# ProPrj_esp_artnet_DMX_2024-10-07.net
KiCad netlist of a schematic drawn in EasyEDA Pro
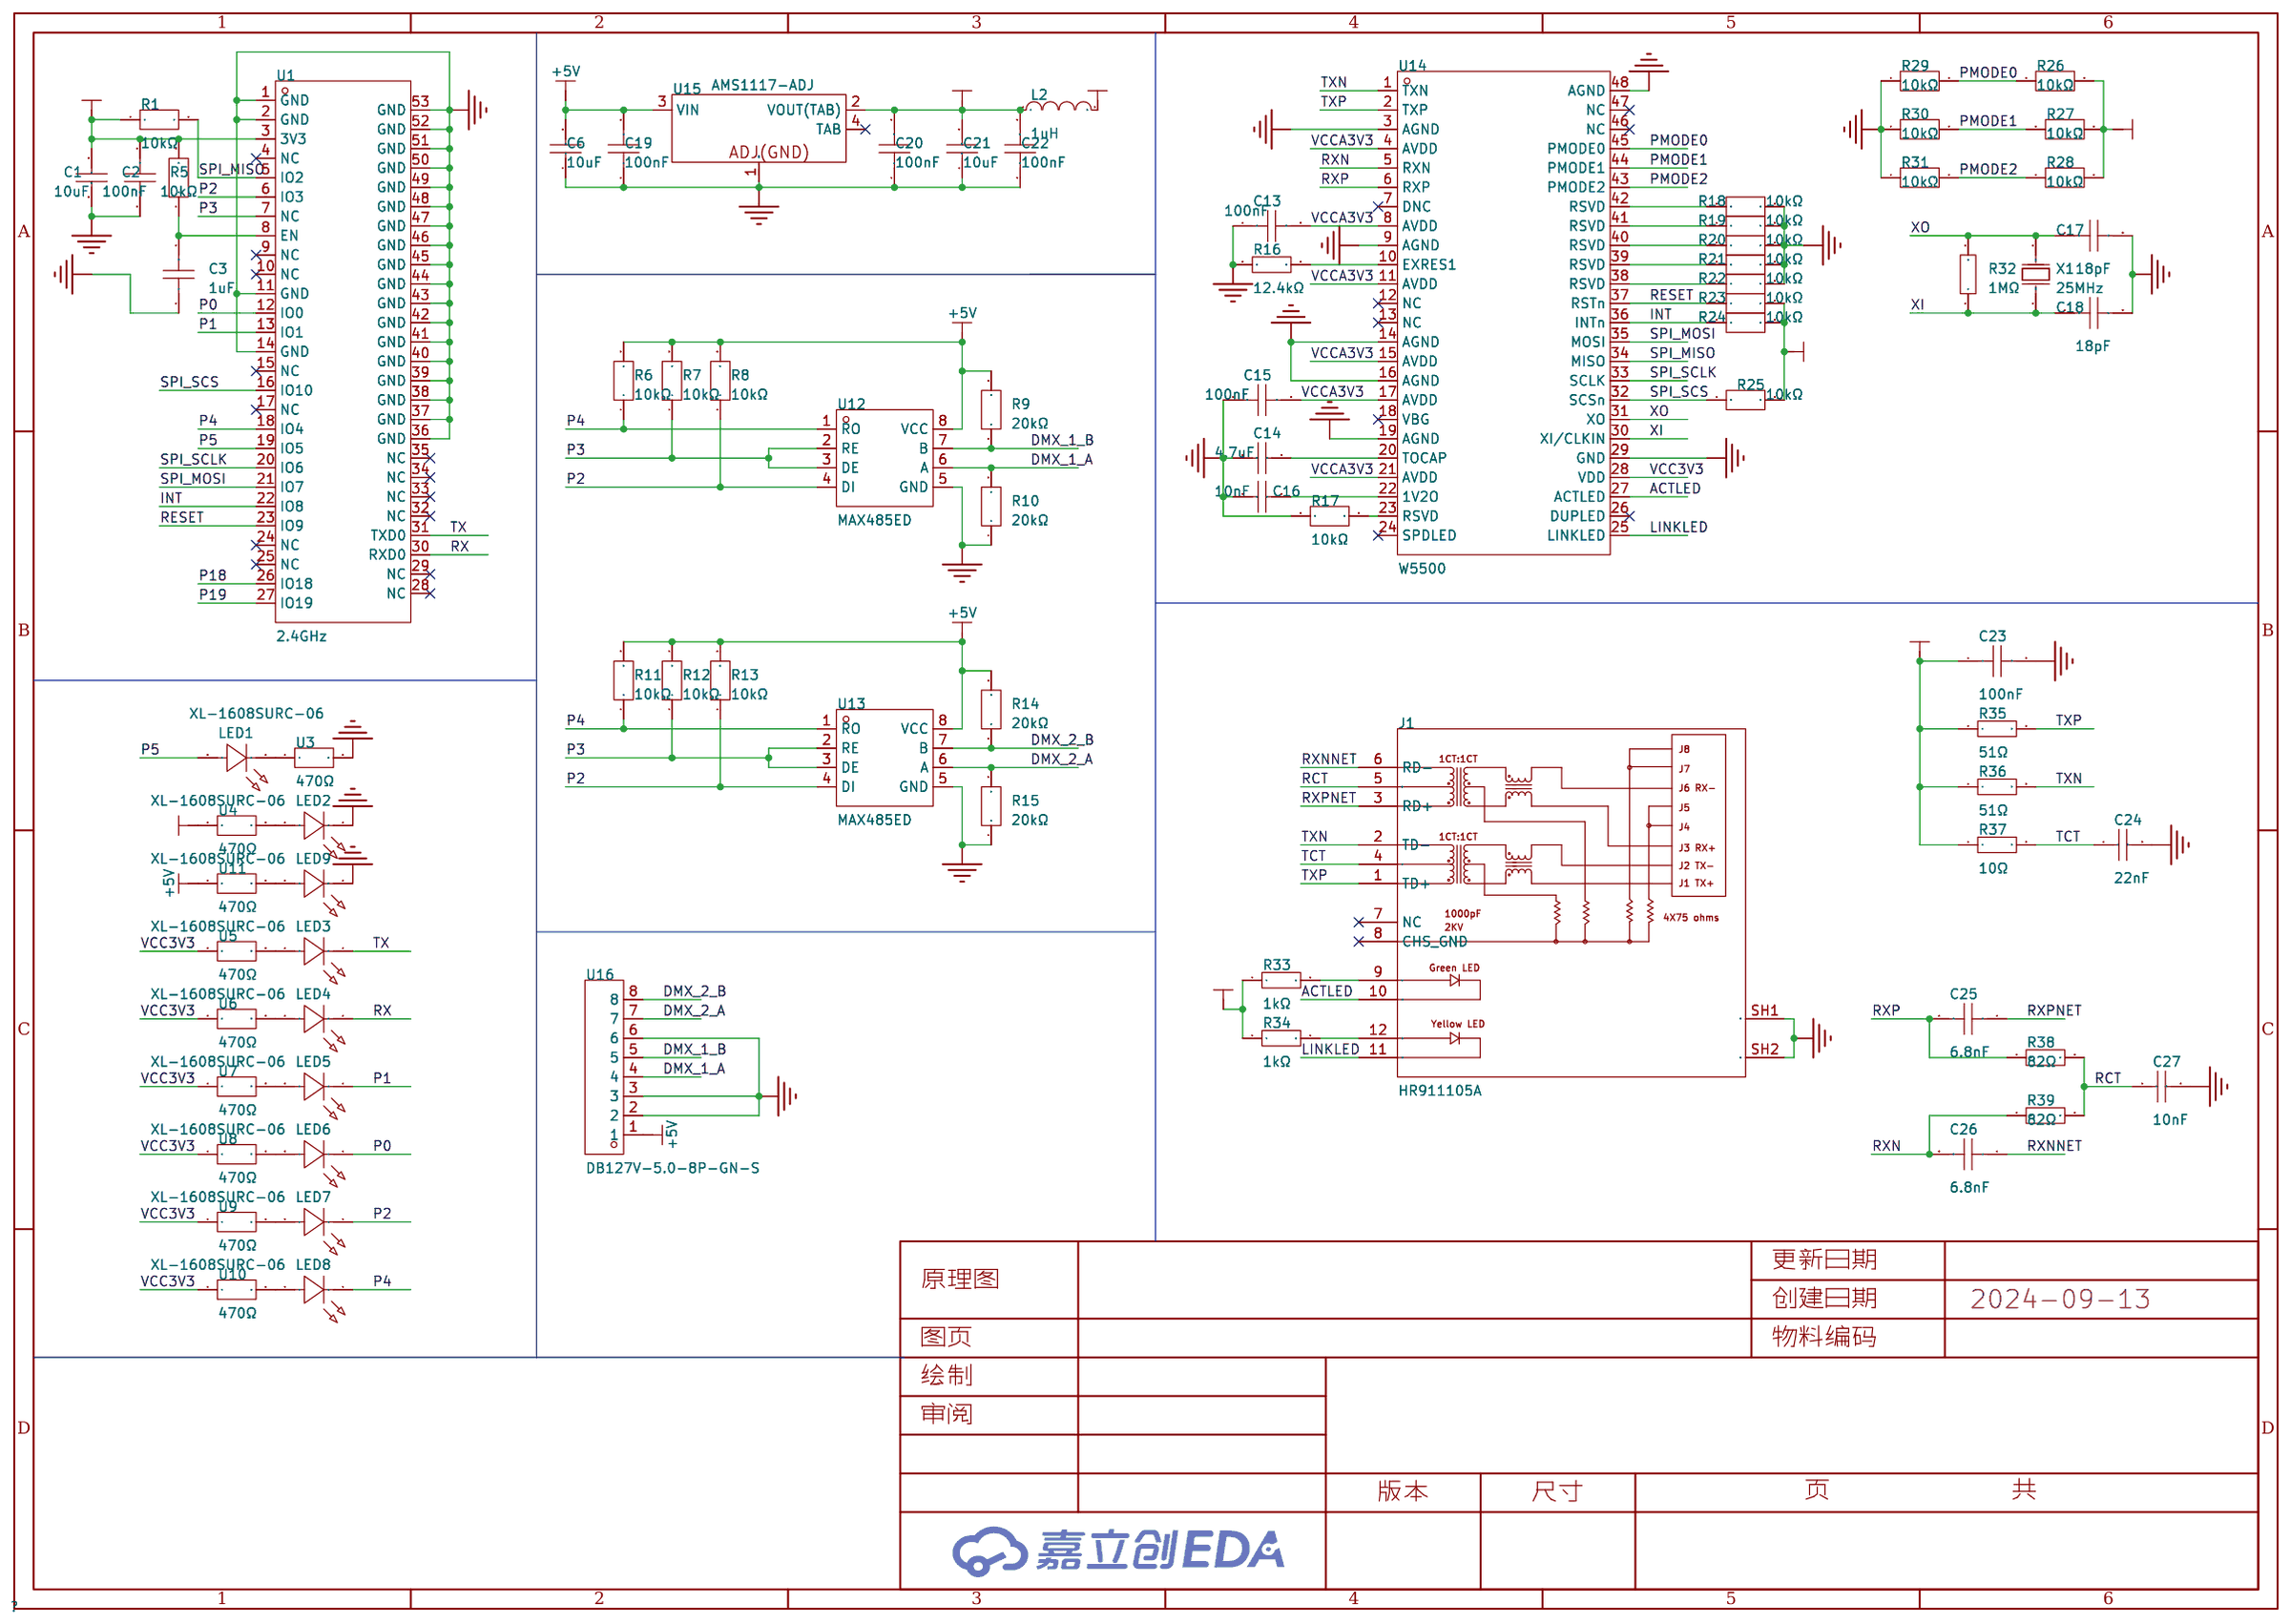
[diagram p0: schematic sheet]

(export (version "E")
  (design (tool "Eeschema 10.0.6"))
  (components
    (comp (ref "C1")
      (value "10uF")
      (footprint "easyedapro:C0805")
      (description "容值:10uF;精度:±10%;额定电压:10V;材质(温度系数):X5R;")
      (fields
        (field (name "Manufacturer Part") "CL21A106KPFNNNE")
        (field (name "Manufacturer") "SAMSUNG(三星)")
      )
      (libsource (lib "easyedapro") (part "CL21A106KPFNNNE"))
    )
    (comp (ref "C2")
      (value "100nF")
      (footprint "easyedapro:C0603")
      (description "容值:100nF;精度:±10%;额定电压:50V;材质(温度系数):X7R;")
      (fields
        (field (name "Manufacturer Part") "CGA0603X7R104K500JT")
        (field (name "Manufacturer") "HRE(芯声)")
      )
      (libsource (lib "easyedapro") (part "CGA0603X7R104K500JT"))
    )
    (comp (ref "C3")
      (value "1uF")
      (footprint "easyedapro:C0603")
      (description "容值:1uF;精度:±10%;额定电压:50V;材质(温度系数):X5R;")
      (fields
        (field (name "Manufacturer Part") "CL10A105KB8NNNC")
        (field (name "Manufacturer") "SAMSUNG(三星)")
      )
      (libsource (lib "easyedapro") (part "CL10A105KB8NNNC"))
    )
    (comp (ref "C6")
      (value "10uF")
      (footprint "easyedapro:C0805")
      (description "容值:10uF;精度:±10%;额定电压:10V;材质(温度系数):X5R;")
      (fields
        (field (name "Manufacturer Part") "CL21A106KPFNNNE")
        (field (name "Manufacturer") "SAMSUNG(三星)")
      )
      (libsource (lib "easyedapro") (part "CL21A106KPFNNNE"))
    )
    (comp (ref "C13")
      (value "100nF")
      (footprint "easyedapro:C0603")
      (description "容值:100nF;精度:±10%;额定电压:50V;材质(温度系数):X7R;")
      (fields
        (field (name "Manufacturer Part") "CGA0603X7R104K500JT")
        (field (name "Manufacturer") "HRE(芯声)")
      )
      (libsource (lib "easyedapro") (part "CGA0603X7R104K500JT"))
    )
    (comp (ref "C14")
      (value "4.7uF")
      (footprint "easyedapro:C0603")
      (description "容值:4.7uF;精度:±10%;额定电压:16V;材质(温度系数):X5R;")
      (fields
        (field (name "Manufacturer Part") "CL10A475KO8NNNC")
        (field (name "Manufacturer") "SAMSUNG(三星)")
      )
      (libsource (lib "easyedapro") (part "CL10A475KO8NNNC"))
    )
    (comp (ref "C15")
      (value "100nF")
      (footprint "easyedapro:C0603")
      (description "容值:100nF;精度:±10%;额定电压:50V;材质(温度系数):X7R;")
      (fields
        (field (name "Manufacturer Part") "CGA0603X7R104K500JT")
        (field (name "Manufacturer") "HRE(芯声)")
      )
      (libsource (lib "easyedapro") (part "CGA0603X7R104K500JT"))
    )
    (comp (ref "C16")
      (value "10nF")
      (footprint "easyedapro:C0603")
      (description "容值:10nF;精度:±10%;额定电压:50V;材质(温度系数):X7R;")
      (fields
        (field (name "Manufacturer Part") "CC0603KRX7R9BB103")
        (field (name "Manufacturer") "YAGEO(国巨)")
      )
      (libsource (lib "easyedapro") (part "CC0603KRX7R9BB103"))
    )
    (comp (ref "C17")
      (value "18pF")
      (footprint "easyedapro:C0603")
      (description "容值:18pF;精度:±5%;额定电压:50V;材质(温度系数):C0G;")
      (fields
        (field (name "Manufacturer Part") "FCC0603N180J500CT")
        (field (name "Manufacturer") "FOJAN(富捷)")
      )
      (libsource (lib "easyedapro") (part "FCC0603N180J500CT"))
    )
    (comp (ref "C18")
      (value "18pF")
      (footprint "easyedapro:C0603")
      (description "容值:18pF;精度:±5%;额定电压:50V;材质(温度系数):C0G;")
      (fields
        (field (name "Manufacturer Part") "FCC0603N180J500CT")
        (field (name "Manufacturer") "FOJAN(富捷)")
      )
      (libsource (lib "easyedapro") (part "FCC0603N180J500CT"))
    )
    (comp (ref "C19")
      (value "100nF")
      (footprint "easyedapro:C0603")
      (description "容值:100nF;精度:±10%;额定电压:50V;材质(温度系数):X7R;")
      (fields
        (field (name "Manufacturer Part") "CGA0603X7R104K500JT")
        (field (name "Manufacturer") "HRE(芯声)")
      )
      (libsource (lib "easyedapro") (part "CGA0603X7R104K500JT"))
    )
    (comp (ref "C20")
      (value "100nF")
      (footprint "easyedapro:C0603")
      (description "容值:100nF;精度:±10%;额定电压:50V;材质(温度系数):X7R;")
      (fields
        (field (name "Manufacturer Part") "CGA0603X7R104K500JT")
        (field (name "Manufacturer") "HRE(芯声)")
      )
      (libsource (lib "easyedapro") (part "CGA0603X7R104K500JT"))
    )
    (comp (ref "C21")
      (value "10uF")
      (footprint "easyedapro:C0805")
      (description "容值:10uF;精度:±10%;额定电压:10V;材质(温度系数):X5R;")
      (fields
        (field (name "Manufacturer Part") "CL21A106KPFNNNE")
        (field (name "Manufacturer") "SAMSUNG(三星)")
      )
      (libsource (lib "easyedapro") (part "CL21A106KPFNNNE"))
    )
    (comp (ref "C22")
      (value "100nF")
      (footprint "easyedapro:C0603")
      (description "容值:100nF;精度:±10%;额定电压:50V;材质(温度系数):X7R;")
      (fields
        (field (name "Manufacturer Part") "CGA0603X7R104K500JT")
        (field (name "Manufacturer") "HRE(芯声)")
      )
      (libsource (lib "easyedapro") (part "CGA0603X7R104K500JT"))
    )
    (comp (ref "C23")
      (value "100nF")
      (footprint "easyedapro:C0603")
      (description "容值:100nF;精度:±10%;额定电压:50V;材质(温度系数):X7R;")
      (fields
        (field (name "Manufacturer Part") "CGA0603X7R104K500JT")
        (field (name "Manufacturer") "HRE(芯声)")
      )
      (libsource (lib "easyedapro") (part "CGA0603X7R104K500JT"))
    )
    (comp (ref "C24")
      (value "22nF")
      (footprint "easyedapro:C0603")
      (description "容值:22nF;精度:±10%;额定电压:50V;材质(温度系数):X7R;")
      (fields
        (field (name "Manufacturer Part") "CL10B223KB8NNNC")
        (field (name "Manufacturer") "SAMSUNG(三星)")
      )
      (libsource (lib "easyedapro") (part "CL10B223KB8NNNC"))
    )
    (comp (ref "C25")
      (value "6.8nF")
      (footprint "easyedapro:C0603")
      (description "容值:6.8nF;精度:±5%;额定电压:50V;材质(温度系数):C0G;")
      (fields
        (field (name "Manufacturer Part") "GRM1885C1H682JA01D")
        (field (name "Manufacturer") "muRata(村田)")
      )
      (libsource (lib "easyedapro") (part "GRM1885C1H682JA01D"))
    )
    (comp (ref "C26")
      (value "6.8nF")
      (footprint "easyedapro:C0603")
      (description "容值:6.8nF;精度:±5%;额定电压:50V;材质(温度系数):C0G;")
      (fields
        (field (name "Manufacturer Part") "GRM1885C1H682JA01D")
        (field (name "Manufacturer") "muRata(村田)")
      )
      (libsource (lib "easyedapro") (part "GRM1885C1H682JA01D"))
    )
    (comp (ref "C27")
      (value "10nF")
      (footprint "easyedapro:C0603")
      (description "容值:10nF;精度:±10%;额定电压:50V;材质(温度系数):X7R;")
      (fields
        (field (name "Manufacturer Part") "CC0603KRX7R9BB103")
        (field (name "Manufacturer") "YAGEO(国巨)")
      )
      (libsource (lib "easyedapro") (part "CC0603KRX7R9BB103"))
    )
    (comp (ref "J1")
      (value "HR911105A")
      (footprint "easyedapro:RJ45-TH_HR911105A")
      (description "连接器类型:RJ45插座;端口数量:1;安装方式:-;屏蔽:-;LED:带LED;等级:-;触头材质:-;触头镀层:-;工作温度范围:-;焊接温度(最大值):-;")
      (fields (field (name "Manufacturer") "HANRUN(汉仁)"))
      (libsource (lib "easyedapro") (part "HR911105A_C12074"))
    )
    (comp (ref "L2")
      (value "1uH")
      (footprint "easyedapro:IND-SMD_L4.4-W4.2")
      (description "电感值:1uH;精度:±20%;额定电流:6A;饱和电流(Isat):7A;类型:一体成型电感;")
      (fields (field (name "Manufacturer Part") "FXL0420-1R0-M") (field (name "Manufacturer") "cjiang(长江微电)"))
      (libsource (lib "easyedapro") (part "FXL0420-1R0-M"))
    )
    (comp (ref "LED1")
      (value "XL-1608SURC-06")
      (footprint "easyedapro:LED0603-RD_RED")
      (description "发光颜色:红色;功率:55mW;正向电流:25mA;主波长:617nm~621nm;透镜颜色:无色透明透镜;色温:-;发光角度:120°;载带方式:正贴;工作温度:-30°C~+85°C;")
      (fields (field (name "Manufacturer") "XINGLIGHT(成兴光)"))
      (libsource (lib "easyedapro") (part "XL-1608SURC-06"))
    )
    (comp (ref "LED2")
      (value "XL-1608SURC-06")
      (footprint "easyedapro:LED0603-RD_RED")
      (description "发光颜色:红色;功率:55mW;正向电流:25mA;主波长:617nm~621nm;透镜颜色:无色透明透镜;色温:-;发光角度:120°;载带方式:正贴;工作温度:-30°C~+85°C;")
      (fields (field (name "Manufacturer") "XINGLIGHT(成兴光)"))
      (libsource (lib "easyedapro") (part "XL-1608SURC-06"))
    )
    (comp (ref "LED3")
      (value "XL-1608SURC-06")
      (footprint "easyedapro:LED0603-RD_RED")
      (description "发光颜色:红色;功率:55mW;正向电流:25mA;主波长:617nm~621nm;透镜颜色:无色透明透镜;色温:-;发光角度:120°;载带方式:正贴;工作温度:-30°C~+85°C;")
      (fields (field (name "Manufacturer") "XINGLIGHT(成兴光)"))
      (libsource (lib "easyedapro") (part "XL-1608SURC-06"))
    )
    (comp (ref "LED4")
      (value "XL-1608SURC-06")
      (footprint "easyedapro:LED0603-RD_RED")
      (description "发光颜色:红色;功率:55mW;正向电流:25mA;主波长:617nm~621nm;透镜颜色:无色透明透镜;色温:-;发光角度:120°;载带方式:正贴;工作温度:-30°C~+85°C;")
      (fields (field (name "Manufacturer") "XINGLIGHT(成兴光)"))
      (libsource (lib "easyedapro") (part "XL-1608SURC-06"))
    )
    (comp (ref "LED5")
      (value "XL-1608SURC-06")
      (footprint "easyedapro:LED0603-RD_RED")
      (description "发光颜色:红色;功率:55mW;正向电流:25mA;主波长:617nm~621nm;透镜颜色:无色透明透镜;色温:-;发光角度:120°;载带方式:正贴;工作温度:-30°C~+85°C;")
      (fields (field (name "Manufacturer") "XINGLIGHT(成兴光)"))
      (libsource (lib "easyedapro") (part "XL-1608SURC-06"))
    )
    (comp (ref "LED6")
      (value "XL-1608SURC-06")
      (footprint "easyedapro:LED0603-RD_RED")
      (description "发光颜色:红色;功率:55mW;正向电流:25mA;主波长:617nm~621nm;透镜颜色:无色透明透镜;色温:-;发光角度:120°;载带方式:正贴;工作温度:-30°C~+85°C;")
      (fields (field (name "Manufacturer") "XINGLIGHT(成兴光)"))
      (libsource (lib "easyedapro") (part "XL-1608SURC-06"))
    )
    (comp (ref "LED7")
      (value "XL-1608SURC-06")
      (footprint "easyedapro:LED0603-RD_RED")
      (description "发光颜色:红色;功率:55mW;正向电流:25mA;主波长:617nm~621nm;透镜颜色:无色透明透镜;色温:-;发光角度:120°;载带方式:正贴;工作温度:-30°C~+85°C;")
      (fields (field (name "Manufacturer") "XINGLIGHT(成兴光)"))
      (libsource (lib "easyedapro") (part "XL-1608SURC-06"))
    )
    (comp (ref "LED8")
      (value "XL-1608SURC-06")
      (footprint "easyedapro:LED0603-RD_RED")
      (description "发光颜色:红色;功率:55mW;正向电流:25mA;主波长:617nm~621nm;透镜颜色:无色透明透镜;色温:-;发光角度:120°;载带方式:正贴;工作温度:-30°C~+85°C;")
      (fields (field (name "Manufacturer") "XINGLIGHT(成兴光)"))
      (libsource (lib "easyedapro") (part "XL-1608SURC-06"))
    )
    (comp (ref "LED9")
      (value "XL-1608SURC-06")
      (footprint "easyedapro:LED0603-RD_RED")
      (description "发光颜色:红色;功率:55mW;正向电流:25mA;主波长:617nm~621nm;透镜颜色:无色透明透镜;色温:-;发光角度:120°;载带方式:正贴;工作温度:-30°C~+85°C;")
      (fields (field (name "Manufacturer") "XINGLIGHT(成兴光)"))
      (libsource (lib "easyedapro") (part "XL-1608SURC-06"))
    )
    (comp (ref "R1")
      (value "10kΩ")
      (footprint "easyedapro:R0603")
      (description "电阻类型:厚膜电阻;阻值:10kΩ;精度:±5%;功率:100mW;最大工作电压:75V;温度系数:±100ppm/°C;")
      (fields (field (name "Manufacturer Part") "FRC0603J103TS") (field (name "Manufacturer") "FOJAN(富捷)"))
      (libsource (lib "easyedapro") (part "FRC0603J103TS"))
    )
    (comp (ref "R5")
      (value "10kΩ")
      (footprint "easyedapro:R0603")
      (description "电阻类型:厚膜电阻;阻值:10kΩ;精度:±5%;功率:100mW;最大工作电压:75V;温度系数:±100ppm/°C;")
      (fields (field (name "Manufacturer Part") "FRC0603J103TS") (field (name "Manufacturer") "FOJAN(富捷)"))
      (libsource (lib "easyedapro") (part "FRC0603J103TS"))
    )
    (comp (ref "R6")
      (value "10kΩ")
      (footprint "easyedapro:R0603")
      (description "电阻类型:厚膜电阻;阻值:10kΩ;精度:±5%;功率:100mW;最大工作电压:75V;温度系数:±100ppm/°C;")
      (fields (field (name "Manufacturer Part") "FRC0603J103TS") (field (name "Manufacturer") "FOJAN(富捷)"))
      (libsource (lib "easyedapro") (part "FRC0603J103TS"))
    )
    (comp (ref "R7")
      (value "10kΩ")
      (footprint "easyedapro:R0603")
      (description "电阻类型:厚膜电阻;阻值:10kΩ;精度:±5%;功率:100mW;最大工作电压:75V;温度系数:±100ppm/°C;")
      (fields (field (name "Manufacturer Part") "FRC0603J103TS") (field (name "Manufacturer") "FOJAN(富捷)"))
      (libsource (lib "easyedapro") (part "FRC0603J103TS"))
    )
    (comp (ref "R8")
      (value "10kΩ")
      (footprint "easyedapro:R0603")
      (description "电阻类型:厚膜电阻;阻值:10kΩ;精度:±5%;功率:100mW;最大工作电压:75V;温度系数:±100ppm/°C;")
      (fields (field (name "Manufacturer Part") "FRC0603J103TS") (field (name "Manufacturer") "FOJAN(富捷)"))
      (libsource (lib "easyedapro") (part "FRC0603J103TS"))
    )
    (comp (ref "R9")
      (value "20kΩ")
      (footprint "easyedapro:R0603")
      (description "电阻类型:薄膜电阻;阻值:20kΩ;精度:±0.1%;功率:100mW;最大工作电压:75V;温度系数:±25ppm/°C;")
      (fields (field (name "Manufacturer Part") "RT0603BRD0720KL") (field (name "Manufacturer") "YAGEO(国巨)"))
      (libsource (lib "easyedapro") (part "RT0603BRD0720KL"))
    )
    (comp (ref "R10")
      (value "20kΩ")
      (footprint "easyedapro:R0603")
      (description "电阻类型:薄膜电阻;阻值:20kΩ;精度:±0.1%;功率:100mW;最大工作电压:75V;温度系数:±25ppm/°C;")
      (fields (field (name "Manufacturer Part") "RT0603BRD0720KL") (field (name "Manufacturer") "YAGEO(国巨)"))
      (libsource (lib "easyedapro") (part "RT0603BRD0720KL"))
    )
    (comp (ref "R11")
      (value "10kΩ")
      (footprint "easyedapro:R0603")
      (description "电阻类型:厚膜电阻;阻值:10kΩ;精度:±5%;功率:100mW;最大工作电压:75V;温度系数:±100ppm/°C;")
      (fields (field (name "Manufacturer Part") "FRC0603J103TS") (field (name "Manufacturer") "FOJAN(富捷)"))
      (libsource (lib "easyedapro") (part "FRC0603J103TS"))
    )
    (comp (ref "R12")
      (value "10kΩ")
      (footprint "easyedapro:R0603")
      (description "电阻类型:厚膜电阻;阻值:10kΩ;精度:±5%;功率:100mW;最大工作电压:75V;温度系数:±100ppm/°C;")
      (fields (field (name "Manufacturer Part") "FRC0603J103TS") (field (name "Manufacturer") "FOJAN(富捷)"))
      (libsource (lib "easyedapro") (part "FRC0603J103TS"))
    )
    (comp (ref "R13")
      (value "10kΩ")
      (footprint "easyedapro:R0603")
      (description "电阻类型:厚膜电阻;阻值:10kΩ;精度:±5%;功率:100mW;最大工作电压:75V;温度系数:±100ppm/°C;")
      (fields (field (name "Manufacturer Part") "FRC0603J103TS") (field (name "Manufacturer") "FOJAN(富捷)"))
      (libsource (lib "easyedapro") (part "FRC0603J103TS"))
    )
    (comp (ref "R14")
      (value "20kΩ")
      (footprint "easyedapro:R0603")
      (description "电阻类型:薄膜电阻;阻值:20kΩ;精度:±0.1%;功率:100mW;最大工作电压:75V;温度系数:±25ppm/°C;")
      (fields (field (name "Manufacturer Part") "RT0603BRD0720KL") (field (name "Manufacturer") "YAGEO(国巨)"))
      (libsource (lib "easyedapro") (part "RT0603BRD0720KL"))
    )
    (comp (ref "R15")
      (value "20kΩ")
      (footprint "easyedapro:R0603")
      (description "电阻类型:薄膜电阻;阻值:20kΩ;精度:±0.1%;功率:100mW;最大工作电压:75V;温度系数:±25ppm/°C;")
      (fields (field (name "Manufacturer Part") "RT0603BRD0720KL") (field (name "Manufacturer") "YAGEO(国巨)"))
      (libsource (lib "easyedapro") (part "RT0603BRD0720KL"))
    )
    (comp (ref "R16")
      (value "12.4kΩ")
      (footprint "easyedapro:R0603")
      (description "电阻类型:厚膜电阻;阻值:12.4kΩ;精度:±1%;功率:100mW;最大工作电压:75V;温度系数:±100ppm/°C;")
      (fields
        (field (name "Manufacturer Part") "0603WAF1242T5E")
        (field (name "Manufacturer") "UNI-ROYAL(厚声)")
      )
      (libsource (lib "easyedapro") (part "0603WAF1242T5E"))
    )
    (comp (ref "R17")
      (value "10kΩ")
      (footprint "easyedapro:R0603")
      (description "电阻类型:厚膜电阻;阻值:10kΩ;精度:±5%;功率:100mW;最大工作电压:75V;温度系数:±100ppm/°C;")
      (fields (field (name "Manufacturer Part") "FRC0603J103TS") (field (name "Manufacturer") "FOJAN(富捷)"))
      (libsource (lib "easyedapro") (part "FRC0603J103TS"))
    )
    (comp (ref "R18")
      (value "10kΩ")
      (footprint "easyedapro:R0603")
      (description "电阻类型:厚膜电阻;阻值:10kΩ;精度:±5%;功率:100mW;最大工作电压:75V;温度系数:±100ppm/°C;")
      (fields (field (name "Manufacturer Part") "FRC0603J103TS") (field (name "Manufacturer") "FOJAN(富捷)"))
      (libsource (lib "easyedapro") (part "FRC0603J103TS"))
    )
    (comp (ref "R19")
      (value "10kΩ")
      (footprint "easyedapro:R0603")
      (description "电阻类型:厚膜电阻;阻值:10kΩ;精度:±5%;功率:100mW;最大工作电压:75V;温度系数:±100ppm/°C;")
      (fields (field (name "Manufacturer Part") "FRC0603J103TS") (field (name "Manufacturer") "FOJAN(富捷)"))
      (libsource (lib "easyedapro") (part "FRC0603J103TS"))
    )
    (comp (ref "R20")
      (value "10kΩ")
      (footprint "easyedapro:R0603")
      (description "电阻类型:厚膜电阻;阻值:10kΩ;精度:±5%;功率:100mW;最大工作电压:75V;温度系数:±100ppm/°C;")
      (fields (field (name "Manufacturer Part") "FRC0603J103TS") (field (name "Manufacturer") "FOJAN(富捷)"))
      (libsource (lib "easyedapro") (part "FRC0603J103TS"))
    )
    (comp (ref "R21")
      (value "10kΩ")
      (footprint "easyedapro:R0603")
      (description "电阻类型:厚膜电阻;阻值:10kΩ;精度:±5%;功率:100mW;最大工作电压:75V;温度系数:±100ppm/°C;")
      (fields (field (name "Manufacturer Part") "FRC0603J103TS") (field (name "Manufacturer") "FOJAN(富捷)"))
      (libsource (lib "easyedapro") (part "FRC0603J103TS"))
    )
    (comp (ref "R22")
      (value "10kΩ")
      (footprint "easyedapro:R0603")
      (description "电阻类型:厚膜电阻;阻值:10kΩ;精度:±5%;功率:100mW;最大工作电压:75V;温度系数:±100ppm/°C;")
      (fields (field (name "Manufacturer Part") "FRC0603J103TS") (field (name "Manufacturer") "FOJAN(富捷)"))
      (libsource (lib "easyedapro") (part "FRC0603J103TS"))
    )
    (comp (ref "R23")
      (value "10kΩ")
      (footprint "easyedapro:R0603")
      (description "电阻类型:厚膜电阻;阻值:10kΩ;精度:±5%;功率:100mW;最大工作电压:75V;温度系数:±100ppm/°C;")
      (fields (field (name "Manufacturer Part") "FRC0603J103TS") (field (name "Manufacturer") "FOJAN(富捷)"))
      (libsource (lib "easyedapro") (part "FRC0603J103TS"))
    )
    (comp (ref "R24")
      (value "10kΩ")
      (footprint "easyedapro:R0603")
      (description "电阻类型:厚膜电阻;阻值:10kΩ;精度:±5%;功率:100mW;最大工作电压:75V;温度系数:±100ppm/°C;")
      (fields (field (name "Manufacturer Part") "FRC0603J103TS") (field (name "Manufacturer") "FOJAN(富捷)"))
      (libsource (lib "easyedapro") (part "FRC0603J103TS"))
    )
    (comp (ref "R25")
      (value "10kΩ")
      (footprint "easyedapro:R0603")
      (description "电阻类型:厚膜电阻;阻值:10kΩ;精度:±5%;功率:100mW;最大工作电压:75V;温度系数:±100ppm/°C;")
      (fields (field (name "Manufacturer Part") "FRC0603J103TS") (field (name "Manufacturer") "FOJAN(富捷)"))
      (libsource (lib "easyedapro") (part "FRC0603J103TS"))
    )
    (comp (ref "R26")
      (value "10kΩ")
      (footprint "easyedapro:R0603")
      (description "电阻类型:厚膜电阻;阻值:10kΩ;精度:±5%;功率:100mW;最大工作电压:75V;温度系数:±100ppm/°C;")
      (fields (field (name "Manufacturer Part") "FRC0603J103TS") (field (name "Manufacturer") "FOJAN(富捷)"))
      (libsource (lib "easyedapro") (part "FRC0603J103TS"))
    )
    (comp (ref "R27")
      (value "10kΩ")
      (footprint "easyedapro:R0603")
      (description "电阻类型:厚膜电阻;阻值:10kΩ;精度:±5%;功率:100mW;最大工作电压:75V;温度系数:±100ppm/°C;")
      (fields (field (name "Manufacturer Part") "FRC0603J103TS") (field (name "Manufacturer") "FOJAN(富捷)"))
      (libsource (lib "easyedapro") (part "FRC0603J103TS"))
    )
    (comp (ref "R28")
      (value "10kΩ")
      (footprint "easyedapro:R0603")
      (description "电阻类型:厚膜电阻;阻值:10kΩ;精度:±5%;功率:100mW;最大工作电压:75V;温度系数:±100ppm/°C;")
      (fields (field (name "Manufacturer Part") "FRC0603J103TS") (field (name "Manufacturer") "FOJAN(富捷)"))
      (libsource (lib "easyedapro") (part "FRC0603J103TS"))
    )
    (comp (ref "R29")
      (value "10kΩ")
      (footprint "easyedapro:R0603")
      (description "电阻类型:厚膜电阻;阻值:10kΩ;精度:±5%;功率:100mW;最大工作电压:75V;温度系数:±100ppm/°C;")
      (fields (field (name "Manufacturer Part") "FRC0603J103TS") (field (name "Manufacturer") "FOJAN(富捷)"))
      (libsource (lib "easyedapro") (part "FRC0603J103TS"))
    )
    (comp (ref "R30")
      (value "10kΩ")
      (footprint "easyedapro:R0603")
      (description "电阻类型:厚膜电阻;阻值:10kΩ;精度:±5%;功率:100mW;最大工作电压:75V;温度系数:±100ppm/°C;")
      (fields (field (name "Manufacturer Part") "FRC0603J103TS") (field (name "Manufacturer") "FOJAN(富捷)"))
      (libsource (lib "easyedapro") (part "FRC0603J103TS"))
    )
    (comp (ref "R31")
      (value "10kΩ")
      (footprint "easyedapro:R0603")
      (description "电阻类型:厚膜电阻;阻值:10kΩ;精度:±5%;功率:100mW;最大工作电压:75V;温度系数:±100ppm/°C;")
      (fields (field (name "Manufacturer Part") "FRC0603J103TS") (field (name "Manufacturer") "FOJAN(富捷)"))
      (libsource (lib "easyedapro") (part "FRC0603J103TS"))
    )
    (comp (ref "R32")
      (value "1MΩ")
      (footprint "easyedapro:R0603")
      (description "电阻类型:厚膜电阻;阻值:1MΩ;精度:±1%;功率:100mW;最大工作电压:75V;温度系数:±100ppm/°C;")
      (fields
        (field (name "Manufacturer Part") "0603WAF1004T5E")
        (field (name "Manufacturer") "UNI-ROYAL(厚声)")
      )
      (libsource (lib "easyedapro") (part "0603WAF1004T5E"))
    )
    (comp (ref "R33")
      (value "1kΩ")
      (footprint "easyedapro:R0603")
      (description "电阻类型:厚膜电阻;阻值:1kΩ;精度:±1%;功率:100mW;最大工作电压:75V;温度系数:±100ppm/°C;")
      (fields
        (field (name "Manufacturer Part") "0603WAF1001T5E")
        (field (name "Manufacturer") "UNI-ROYAL(厚声)")
      )
      (libsource (lib "easyedapro") (part "0603WAF1001T5E"))
    )
    (comp (ref "R34")
      (value "1kΩ")
      (footprint "easyedapro:R0603")
      (description "电阻类型:厚膜电阻;阻值:1kΩ;精度:±1%;功率:100mW;最大工作电压:75V;温度系数:±100ppm/°C;")
      (fields
        (field (name "Manufacturer Part") "0603WAF1001T5E")
        (field (name "Manufacturer") "UNI-ROYAL(厚声)")
      )
      (libsource (lib "easyedapro") (part "0603WAF1001T5E"))
    )
    (comp (ref "R35")
      (value "51Ω")
      (footprint "easyedapro:R0603")
      (description "电阻类型:厚膜电阻;阻值:51Ω;精度:±1%;功率:100mW;最大工作电压:75V;温度系数:±100ppm/°C;")
      (fields
        (field (name "Manufacturer Part") "0603WAF510JT5E")
        (field (name "Manufacturer") "UNI-ROYAL(厚声)")
      )
      (libsource (lib "easyedapro") (part "0603WAF510JT5E"))
    )
    (comp (ref "R36")
      (value "51Ω")
      (footprint "easyedapro:R0603")
      (description "电阻类型:厚膜电阻;阻值:51Ω;精度:±1%;功率:100mW;最大工作电压:75V;温度系数:±100ppm/°C;")
      (fields
        (field (name "Manufacturer Part") "0603WAF510JT5E")
        (field (name "Manufacturer") "UNI-ROYAL(厚声)")
      )
      (libsource (lib "easyedapro") (part "0603WAF510JT5E"))
    )
    (comp (ref "R37")
      (value "10Ω")
      (footprint "easyedapro:R0603")
      (description "电阻类型:厚膜电阻;阻值:10Ω;精度:±1%;功率:100mW;最大工作电压:75V;温度系数:±400ppm/°C;")
      (fields
        (field (name "Manufacturer Part") "0603WAF100JT5E")
        (field (name "Manufacturer") "UNI-ROYAL(厚声)")
      )
      (libsource (lib "easyedapro") (part "0603WAF100JT5E"))
    )
    (comp (ref "R38")
      (value "82Ω")
      (footprint "easyedapro:R0603")
      (description "电阻类型:厚膜电阻;阻值:82Ω;精度:±1%;功率:100mW;最大工作电压:75V;温度系数:±100ppm/°C;")
      (fields
        (field (name "Manufacturer Part") "0603WAF820JT5E")
        (field (name "Manufacturer") "UNI-ROYAL(厚声)")
      )
      (libsource (lib "easyedapro") (part "0603WAF820JT5E"))
    )
    (comp (ref "R39")
      (value "82Ω")
      (footprint "easyedapro:R0603")
      (description "电阻类型:厚膜电阻;阻值:82Ω;精度:±1%;功率:100mW;最大工作电压:75V;温度系数:±100ppm/°C;")
      (fields
        (field (name "Manufacturer Part") "0603WAF820JT5E")
        (field (name "Manufacturer") "UNI-ROYAL(厚声)")
      )
      (libsource (lib "easyedapro") (part "0603WAF820JT5E"))
    )
    (comp (ref "U1")
      (value "2.4GHz")
      (footprint "easyedapro:WIFIM-SMD_ESP32-C3-MINI-1")
      (description "核心处理器:ESP32-C3芯片;频率:2.4GHz;天线形式:板载PCB天线;发射功率:-;接收灵敏度:-89dBm;")
      (fields
        (field (name "Manufacturer Part") "ESP32-C3-MINI-1")
        (field (name "Manufacturer") "RF Crazy(智汉)")
      )
      (libsource (lib "easyedapro") (part "ESP32-C3-MINI-1"))
    )
    (comp (ref "U3")
      (value "470Ω")
      (footprint "easyedapro:R0805")
      (description "电阻类型:厚膜电阻;阻值:470Ω;精度:±5%;功率:125mW;最大工作电压:150V;温度系数:±100ppm/°C;")
      (fields (field (name "Manufacturer Part") "FRC0805J471 TS") (field (name "Manufacturer") "FOJAN(富捷)"))
      (libsource (lib "easyedapro") (part "FRC0805J471 TS"))
    )
    (comp (ref "U4")
      (value "470Ω")
      (footprint "easyedapro:R0805")
      (description "电阻类型:厚膜电阻;阻值:470Ω;精度:±5%;功率:125mW;最大工作电压:150V;温度系数:±100ppm/°C;")
      (fields (field (name "Manufacturer Part") "FRC0805J471 TS") (field (name "Manufacturer") "FOJAN(富捷)"))
      (libsource (lib "easyedapro") (part "FRC0805J471 TS"))
    )
    (comp (ref "U5")
      (value "470Ω")
      (footprint "easyedapro:R0805")
      (description "电阻类型:厚膜电阻;阻值:470Ω;精度:±5%;功率:125mW;最大工作电压:150V;温度系数:±100ppm/°C;")
      (fields (field (name "Manufacturer Part") "FRC0805J471 TS") (field (name "Manufacturer") "FOJAN(富捷)"))
      (libsource (lib "easyedapro") (part "FRC0805J471 TS"))
    )
    (comp (ref "U6")
      (value "470Ω")
      (footprint "easyedapro:R0805")
      (description "电阻类型:厚膜电阻;阻值:470Ω;精度:±5%;功率:125mW;最大工作电压:150V;温度系数:±100ppm/°C;")
      (fields (field (name "Manufacturer Part") "FRC0805J471 TS") (field (name "Manufacturer") "FOJAN(富捷)"))
      (libsource (lib "easyedapro") (part "FRC0805J471 TS"))
    )
    (comp (ref "U7")
      (value "470Ω")
      (footprint "easyedapro:R0805")
      (description "电阻类型:厚膜电阻;阻值:470Ω;精度:±5%;功率:125mW;最大工作电压:150V;温度系数:±100ppm/°C;")
      (fields (field (name "Manufacturer Part") "FRC0805J471 TS") (field (name "Manufacturer") "FOJAN(富捷)"))
      (libsource (lib "easyedapro") (part "FRC0805J471 TS"))
    )
    (comp (ref "U8")
      (value "470Ω")
      (footprint "easyedapro:R0805")
      (description "电阻类型:厚膜电阻;阻值:470Ω;精度:±5%;功率:125mW;最大工作电压:150V;温度系数:±100ppm/°C;")
      (fields (field (name "Manufacturer Part") "FRC0805J471 TS") (field (name "Manufacturer") "FOJAN(富捷)"))
      (libsource (lib "easyedapro") (part "FRC0805J471 TS"))
    )
    (comp (ref "U9")
      (value "470Ω")
      (footprint "easyedapro:R0805")
      (description "电阻类型:厚膜电阻;阻值:470Ω;精度:±5%;功率:125mW;最大工作电压:150V;温度系数:±100ppm/°C;")
      (fields (field (name "Manufacturer Part") "FRC0805J471 TS") (field (name "Manufacturer") "FOJAN(富捷)"))
      (libsource (lib "easyedapro") (part "FRC0805J471 TS"))
    )
    (comp (ref "U10")
      (value "470Ω")
      (footprint "easyedapro:R0805")
      (description "电阻类型:厚膜电阻;阻值:470Ω;精度:±5%;功率:125mW;最大工作电压:150V;温度系数:±100ppm/°C;")
      (fields (field (name "Manufacturer Part") "FRC0805J471 TS") (field (name "Manufacturer") "FOJAN(富捷)"))
      (libsource (lib "easyedapro") (part "FRC0805J471 TS"))
    )
    (comp (ref "U11")
      (value "470Ω")
      (footprint "easyedapro:R0805")
      (description "电阻类型:厚膜电阻;阻值:470Ω;精度:±5%;功率:125mW;最大工作电压:150V;温度系数:±100ppm/°C;")
      (fields (field (name "Manufacturer Part") "FRC0805J471 TS") (field (name "Manufacturer") "FOJAN(富捷)"))
      (libsource (lib "easyedapro") (part "FRC0805J471 TS"))
    )
    (comp (ref "U12")
      (value "MAX485ED")
      (footprint "easyedapro:SOP-8_L4.9-W3.9-P1.27-LS6.0-BL")
      (fields (field (name "Manufacturer") "HTC"))
      (libsource (lib "easyedapro") (part "MAX485ED"))
    )
    (comp (ref "U13")
      (value "MAX485ED")
      (footprint "easyedapro:SOP-8_L4.9-W3.9-P1.27-LS6.0-BL")
      (fields (field (name "Manufacturer") "HTC"))
      (libsource (lib "easyedapro") (part "MAX485ED"))
    )
    (comp (ref "U14")
      (value "W5500")
      (footprint "easyedapro:LQFP-48_L7.0-W7.0-P0.50-LS9.0-BL")
      (fields (field (name "Manufacturer") "WIZNET"))
      (libsource (lib "easyedapro") (part "W5500"))
    )
    (comp (ref "U15")
      (value "AMS1117-ADJ")
      (footprint "easyedapro:SOT-223_L6.7-W3.5-P2.30-BR")
      (description "输出类型:-;")
      (fields (field (name "Manufacturer") "UMW(友台半导体)"))
      (libsource (lib "easyedapro") (part "AMS1117-ADJ_C347224"))
    )
    (comp (ref "U16")
      (value "DB127V-5.0-8P-GN-S")
      (footprint "easyedapro:CONN-TH_8P-P5.00_DB127V-5.0-8P-GN-S")
      (fields (field (name "Manufacturer") "DORABO(地博电气)"))
      (libsource (lib "easyedapro") (part "DB127V-5.0-8P-GN-S"))
    )
    (comp (ref "X1")
      (value "25MHz")
      (footprint "easyedapro:HC-49US_L11.5-W4.5-P4.88")
      (description "晶振类型:直插晶振;频率:25MHz;常温频差:±20ppm;外接负载电容:20pF;")
      (fields (field (name "Manufacturer Part") "B25000J288") (field (name "Manufacturer") "ECEC(东晶)"))
      (libsource (lib "easyedapro") (part "B25000J288"))
    )
  )
  (nets
    (net (code "1") (name "+5V") (class "Default")
      (node (ref "C19") (pin "2") (pinfunction "2_2") (pintype "unspecified"))
      (node (ref "C6") (pin "2") (pinfunction "2_2") (pintype "input"))
      (node (ref "R11") (pin "2") (pinfunction "2_2") (pintype "unspecified"))
      (node (ref "R12") (pin "2") (pinfunction "2_2") (pintype "unspecified"))
      (node (ref "R13") (pin "2") (pinfunction "2_2") (pintype "unspecified"))
      (node (ref "R14") (pin "2") (pinfunction "2_2") (pintype "unspecified"))
      (node (ref "R6") (pin "2") (pinfunction "2_2") (pintype "unspecified"))
      (node (ref "R7") (pin "2") (pinfunction "2_2") (pintype "unspecified"))
      (node (ref "R8") (pin "2") (pinfunction "2_2") (pintype "unspecified"))
      (node (ref "R9") (pin "2") (pinfunction "2_2") (pintype "unspecified"))
      (node (ref "U11") (pin "1") (pinfunction "1_1") (pintype "unspecified"))
      (node (ref "U12") (pin "8") (pinfunction "VCC_8") (pintype "unspecified"))
      (node (ref "U13") (pin "8") (pinfunction "VCC_8") (pintype "unspecified"))
      (node (ref "U15") (pin "3") (pinfunction "VIN_3") (pintype "unspecified"))
      (node (ref "U16") (pin "1") (pinfunction "1_1") (pintype "unspecified"))
    )
    (net (code "2") (name "/ACTLED") (class "Default")
      (node (ref "J1") (pin "10") (pinfunction "10_10") (pintype "unspecified"))
      (node (ref "U14") (pin "27") (pinfunction "ACTLED_27") (pintype "unspecified"))
    )
    (net (code "3") (name "/DMX_1_A") (class "Default")
      (node (ref "R10") (pin "2") (pinfunction "2_2") (pintype "unspecified"))
      (node (ref "U12") (pin "6") (pinfunction "A_6") (pintype "unspecified"))
      (node (ref "U16") (pin "4") (pinfunction "4_4") (pintype "unspecified"))
    )
    (net (code "4") (name "/DMX_1_B") (class "Default")
      (node (ref "R9") (pin "1") (pinfunction "1_1") (pintype "unspecified"))
      (node (ref "U12") (pin "7") (pinfunction "B_7") (pintype "unspecified"))
      (node (ref "U16") (pin "5") (pinfunction "5_5") (pintype "unspecified"))
    )
    (net (code "5") (name "/DMX_2_A") (class "Default")
      (node (ref "R15") (pin "2") (pinfunction "2_2") (pintype "unspecified"))
      (node (ref "U13") (pin "6") (pinfunction "A_6") (pintype "unspecified"))
      (node (ref "U16") (pin "7") (pinfunction "7_7") (pintype "unspecified"))
    )
    (net (code "6") (name "/DMX_2_B") (class "Default")
      (node (ref "R14") (pin "1") (pinfunction "1_1") (pintype "unspecified"))
      (node (ref "U13") (pin "7") (pinfunction "B_7") (pintype "unspecified"))
      (node (ref "U16") (pin "8") (pinfunction "8_8") (pintype "unspecified"))
    )
    (net (code "7") (name "/INT") (class "Default")
      (node (ref "R24") (pin "1") (pinfunction "1_1") (pintype "unspecified"))
      (node (ref "U1") (pin "22") (pinfunction "IO8_22") (pintype "unspecified"))
      (node (ref "U14") (pin "36") (pinfunction "INTn_36") (pintype "unspecified"))
    )
    (net (code "8") (name "/LINKLED") (class "Default")
      (node (ref "J1") (pin "11") (pinfunction "11_11") (pintype "unspecified"))
      (node (ref "U14") (pin "25") (pinfunction "LINKLED_25") (pintype "unspecified"))
    )
    (net (code "9") (name "/P0") (class "Default")
      (node (ref "LED6") (pin "1") (pinfunction "K_1") (pintype "unspecified"))
      (node (ref "U1") (pin "12") (pinfunction "IO0_12") (pintype "unspecified"))
    )
    (net (code "10") (name "/P1") (class "Default")
      (node (ref "LED5") (pin "1") (pinfunction "K_1") (pintype "unspecified"))
      (node (ref "U1") (pin "13") (pinfunction "IO1_13") (pintype "unspecified"))
    )
    (net (code "11") (name "/P2") (class "Default")
      (node (ref "LED7") (pin "1") (pinfunction "K_1") (pintype "unspecified"))
      (node (ref "R13") (pin "1") (pinfunction "1_1") (pintype "unspecified"))
      (node (ref "R8") (pin "1") (pinfunction "1_1") (pintype "unspecified"))
      (node (ref "U1") (pin "6") (pinfunction "IO3_6") (pintype "unspecified"))
      (node (ref "U12") (pin "4") (pinfunction "DI_4") (pintype "unspecified"))
      (node (ref "U13") (pin "4") (pinfunction "DI_4") (pintype "unspecified"))
    )
    (net (code "12") (name "/P3") (class "Default")
      (node (ref "R12") (pin "1") (pinfunction "1_1") (pintype "unspecified"))
      (node (ref "R7") (pin "1") (pinfunction "1_1") (pintype "unspecified"))
      (node (ref "U1") (pin "7") (pinfunction "NC_7") (pintype "unspecified"))
      (node (ref "U12") (pin "2") (pinfunction "RE_2") (pintype "unspecified"))
      (node (ref "U12") (pin "3") (pinfunction "DE_3") (pintype "unspecified"))
      (node (ref "U13") (pin "2") (pinfunction "RE_2") (pintype "unspecified"))
      (node (ref "U13") (pin "3") (pinfunction "DE_3") (pintype "unspecified"))
    )
    (net (code "13") (name "/P4") (class "Default")
      (node (ref "LED8") (pin "1") (pinfunction "K_1") (pintype "unspecified"))
      (node (ref "R11") (pin "1") (pinfunction "1_1") (pintype "unspecified"))
      (node (ref "R6") (pin "1") (pinfunction "1_1") (pintype "unspecified"))
      (node (ref "U1") (pin "18") (pinfunction "IO4_18") (pintype "unspecified"))
      (node (ref "U12") (pin "1") (pinfunction "RO_1") (pintype "unspecified"))
      (node (ref "U13") (pin "1") (pinfunction "RO_1") (pintype "unspecified"))
    )
    (net (code "14") (name "/P5") (class "Default")
      (node (ref "LED1") (pin "2") (pinfunction "A_2") (pintype "unspecified"))
      (node (ref "U1") (pin "19") (pinfunction "IO5_19") (pintype "unspecified"))
    )
    (net (code "15") (name "/P18") (class "Default")
      (node (ref "U1") (pin "26") (pinfunction "IO18_26") (pintype "unspecified"))
    )
    (net (code "16") (name "/P19") (class "Default")
      (node (ref "U1") (pin "27") (pinfunction "IO19_27") (pintype "unspecified"))
    )
    (net (code "17") (name "/PMODE0") (class "Default")
      (node (ref "R26") (pin "1") (pinfunction "1_1") (pintype "unspecified"))
      (node (ref "R29") (pin "2") (pinfunction "2_2") (pintype "unspecified"))
      (node (ref "U14") (pin "45") (pinfunction "PMODE0_45") (pintype "unspecified"))
    )
    (net (code "18") (name "/PMODE1") (class "Default")
      (node (ref "R27") (pin "1") (pinfunction "1_1") (pintype "unspecified"))
      (node (ref "R30") (pin "2") (pinfunction "2_2") (pintype "unspecified"))
      (node (ref "U14") (pin "44") (pinfunction "PMODE1_44") (pintype "unspecified"))
    )
    (net (code "19") (name "/PMODE2") (class "Default")
      (node (ref "R28") (pin "1") (pinfunction "1_1") (pintype "unspecified"))
      (node (ref "R31") (pin "2") (pinfunction "2_2") (pintype "unspecified"))
      (node (ref "U14") (pin "43") (pinfunction "PMODE2_43") (pintype "unspecified"))
    )
    (net (code "20") (name "/RCT") (class "Default")
      (node (ref "C27") (pin "1") (pinfunction "1_1") (pintype "input"))
      (node (ref "J1") (pin "5") (pinfunction "5_5") (pintype "unspecified"))
      (node (ref "R38") (pin "2") (pinfunction "2_2") (pintype "input"))
      (node (ref "R39") (pin "2") (pinfunction "2_2") (pintype "input"))
    )
    (net (code "21") (name "/RESET") (class "Default")
      (node (ref "R23") (pin "1") (pinfunction "1_1") (pintype "unspecified"))
      (node (ref "U1") (pin "23") (pinfunction "IO9_23") (pintype "unspecified"))
      (node (ref "U14") (pin "37") (pinfunction "RSTn_37") (pintype "unspecified"))
    )
    (net (code "22") (name "/RX") (class "Default")
      (node (ref "LED4") (pin "1") (pinfunction "K_1") (pintype "unspecified"))
      (node (ref "U1") (pin "30") (pinfunction "RXD0_30") (pintype "unspecified"))
    )
    (net (code "23") (name "/RXN") (class "Default")
      (node (ref "C26") (pin "2") (pinfunction "2_2") (pintype "unspecified"))
      (node (ref "R39") (pin "1") (pinfunction "1_1") (pintype "input"))
      (node (ref "U14") (pin "5") (pinfunction "RXN_5") (pintype "unspecified"))
    )
    (net (code "24") (name "/RXNNET") (class "Default")
      (node (ref "C26") (pin "1") (pinfunction "1_1") (pintype "unspecified"))
      (node (ref "J1") (pin "6") (pinfunction "RD-_6") (pintype "unspecified"))
    )
    (net (code "25") (name "/RXP") (class "Default")
      (node (ref "C25") (pin "2") (pinfunction "2_2") (pintype "unspecified"))
      (node (ref "R38") (pin "1") (pinfunction "1_1") (pintype "input"))
      (node (ref "U14") (pin "6") (pinfunction "RXP_6") (pintype "unspecified"))
    )
    (net (code "26") (name "/RXPNET") (class "Default")
      (node (ref "C25") (pin "1") (pinfunction "1_1") (pintype "unspecified"))
      (node (ref "J1") (pin "3") (pinfunction "RD+_3") (pintype "unspecified"))
    )
    (net (code "27") (name "/SPI_MISO") (class "Default")
      (node (ref "R1") (pin "2") (pinfunction "2_2") (pintype "unspecified"))
      (node (ref "U1") (pin "5") (pinfunction "IO2_5") (pintype "unspecified"))
      (node (ref "U14") (pin "34") (pinfunction "MISO_34") (pintype "unspecified"))
    )
    (net (code "28") (name "/SPI_MOSI") (class "Default")
      (node (ref "U1") (pin "21") (pinfunction "IO7_21") (pintype "unspecified"))
      (node (ref "U14") (pin "35") (pinfunction "MOSI_35") (pintype "unspecified"))
    )
    (net (code "29") (name "/SPI_SCLK") (class "Default")
      (node (ref "U1") (pin "20") (pinfunction "IO6_20") (pintype "unspecified"))
      (node (ref "U14") (pin "33") (pinfunction "SCLK_33") (pintype "unspecified"))
    )
    (net (code "30") (name "/SPI_SCS") (class "Default")
      (node (ref "R25") (pin "1") (pinfunction "1_1") (pintype "unspecified"))
      (node (ref "U1") (pin "16") (pinfunction "IO10_16") (pintype "unspecified"))
      (node (ref "U14") (pin "32") (pinfunction "SCSn_32") (pintype "unspecified"))
    )
    (net (code "31") (name "/TCT") (class "Default")
      (node (ref "C24") (pin "1") (pinfunction "1_1") (pintype "input"))
      (node (ref "J1") (pin "4") (pinfunction "4_4") (pintype "unspecified"))
      (node (ref "R37") (pin "2") (pinfunction "2_2") (pintype "input"))
    )
    (net (code "32") (name "/TX") (class "Default")
      (node (ref "LED3") (pin "1") (pinfunction "K_1") (pintype "unspecified"))
      (node (ref "U1") (pin "31") (pinfunction "TXD0_31") (pintype "unspecified"))
    )
    (net (code "33") (name "/TXN") (class "Default")
      (node (ref "J1") (pin "2") (pinfunction "TD-_2") (pintype "unspecified"))
      (node (ref "R36") (pin "2") (pinfunction "2_2") (pintype "input"))
      (node (ref "U14") (pin "1") (pinfunction "TXN_1") (pintype "unspecified"))
    )
    (net (code "34") (name "/TXP") (class "Default")
      (node (ref "J1") (pin "1") (pinfunction "TD+_1") (pintype "unspecified"))
      (node (ref "R35") (pin "2") (pinfunction "2_2") (pintype "input"))
      (node (ref "U14") (pin "2") (pinfunction "TXP_2") (pintype "unspecified"))
    )
    (net (code "35") (name "/XI") (class "Default")
      (node (ref "C18") (pin "1") (pinfunction "1_1") (pintype "unspecified"))
      (node (ref "R32") (pin "1") (pinfunction "1_1") (pintype "input"))
      (node (ref "U14") (pin "30") (pinfunction "XI/CLKIN_30") (pintype "unspecified"))
      (node (ref "X1") (pin "1") (pinfunction "OSC1_1") (pintype "input"))
    )
    (net (code "36") (name "/XO") (class "Default")
      (node (ref "C17") (pin "1") (pinfunction "1_1") (pintype "unspecified"))
      (node (ref "R32") (pin "2") (pinfunction "2_2") (pintype "input"))
      (node (ref "U14") (pin "31") (pinfunction "XO_31") (pintype "unspecified"))
      (node (ref "X1") (pin "2") (pinfunction "OSC2_2") (pintype "input"))
    )
    (net (code "37") (name "GND") (class "Default")
      (node (ref "C1") (pin "1") (pinfunction "1_1") (pintype "input"))
      (node (ref "C13") (pin "1") (pinfunction "1_1") (pintype "unspecified"))
      (node (ref "C14") (pin "1") (pinfunction "1_1") (pintype "input"))
      (node (ref "C15") (pin "1") (pinfunction "1_1") (pintype "unspecified"))
      (node (ref "C16") (pin "1") (pinfunction "1_1") (pintype "input"))
      (node (ref "C17") (pin "2") (pinfunction "2_2") (pintype "unspecified"))
      (node (ref "C18") (pin "2") (pinfunction "2_2") (pintype "unspecified"))
      (node (ref "C19") (pin "1") (pinfunction "1_1") (pintype "unspecified"))
      (node (ref "C2") (pin "1") (pinfunction "1_1") (pintype "unspecified"))
      (node (ref "C20") (pin "1") (pinfunction "1_1") (pintype "unspecified"))
      (node (ref "C21") (pin "1") (pinfunction "1_1") (pintype "input"))
      (node (ref "C22") (pin "1") (pinfunction "1_1") (pintype "unspecified"))
      (node (ref "C23") (pin "2") (pinfunction "2_2") (pintype "unspecified"))
      (node (ref "C24") (pin "2") (pinfunction "2_2") (pintype "input"))
      (node (ref "C27") (pin "2") (pinfunction "2_2") (pintype "input"))
      (node (ref "C3") (pin "1") (pinfunction "1_1") (pintype "unspecified"))
      (node (ref "C6") (pin "1") (pinfunction "1_1") (pintype "input"))
      (node (ref "J1") (pin "SH1") (pinfunction "SH1_SH1") (pintype "unspecified"))
      (node (ref "J1") (pin "SH2") (pinfunction "SH2_SH2") (pintype "unspecified"))
      (node (ref "LED2") (pin "1") (pinfunction "K_1") (pintype "unspecified"))
      (node (ref "LED9") (pin "1") (pinfunction "K_1") (pintype "unspecified"))
      (node (ref "R10") (pin "1") (pinfunction "1_1") (pintype "unspecified"))
      (node (ref "R15") (pin "1") (pinfunction "1_1") (pintype "unspecified"))
      (node (ref "R16") (pin "1") (pinfunction "1_1") (pintype "input"))
      (node (ref "R17") (pin "1") (pinfunction "1_1") (pintype "unspecified"))
      (node (ref "R18") (pin "2") (pinfunction "2_2") (pintype "unspecified"))
      (node (ref "R19") (pin "2") (pinfunction "2_2") (pintype "unspecified"))
      (node (ref "R20") (pin "2") (pinfunction "2_2") (pintype "unspecified"))
      (node (ref "R21") (pin "2") (pinfunction "2_2") (pintype "unspecified"))
      (node (ref "R22") (pin "2") (pinfunction "2_2") (pintype "unspecified"))
      (node (ref "R29") (pin "1") (pinfunction "1_1") (pintype "unspecified"))
      (node (ref "R30") (pin "1") (pinfunction "1_1") (pintype "unspecified"))
      (node (ref "R31") (pin "1") (pinfunction "1_1") (pintype "unspecified"))
      (node (ref "U1") (pin "1") (pinfunction "GND_1") (pintype "unspecified"))
      (node (ref "U1") (pin "11") (pinfunction "GND_11") (pintype "unspecified"))
      (node (ref "U1") (pin "14") (pinfunction "GND_14") (pintype "unspecified"))
      (node (ref "U1") (pin "2") (pinfunction "GND_2") (pintype "unspecified"))
      (node (ref "U1") (pin "36") (pinfunction "GND_36") (pintype "unspecified"))
      (node (ref "U1") (pin "37") (pinfunction "GND_37") (pintype "unspecified"))
      (node (ref "U1") (pin "38") (pinfunction "GND_38") (pintype "unspecified"))
      (node (ref "U1") (pin "39") (pinfunction "GND_39") (pintype "unspecified"))
      (node (ref "U1") (pin "40") (pinfunction "GND_40") (pintype "unspecified"))
      (node (ref "U1") (pin "41") (pinfunction "GND_41") (pintype "unspecified"))
      (node (ref "U1") (pin "42") (pinfunction "GND_42") (pintype "unspecified"))
      (node (ref "U1") (pin "43") (pinfunction "GND_43") (pintype "unspecified"))
      (node (ref "U1") (pin "44") (pinfunction "GND_44") (pintype "unspecified"))
      (node (ref "U1") (pin "45") (pinfunction "GND_45") (pintype "unspecified"))
      (node (ref "U1") (pin "46") (pinfunction "GND_46") (pintype "unspecified"))
      (node (ref "U1") (pin "47") (pinfunction "GND_47") (pintype "unspecified"))
      (node (ref "U1") (pin "48") (pinfunction "GND_48") (pintype "unspecified"))
      (node (ref "U1") (pin "49") (pinfunction "GND_49") (pintype "unspecified"))
      (node (ref "U1") (pin "50") (pinfunction "GND_50") (pintype "unspecified"))
      (node (ref "U1") (pin "51") (pinfunction "GND_51") (pintype "unspecified"))
      (node (ref "U1") (pin "52") (pinfunction "GND_52") (pintype "unspecified"))
      (node (ref "U1") (pin "53") (pinfunction "GND_53") (pintype "unspecified"))
      (node (ref "U12") (pin "5") (pinfunction "GND_5") (pintype "unspecified"))
      (node (ref "U13") (pin "5") (pinfunction "GND_5") (pintype "unspecified"))
      (node (ref "U14") (pin "14") (pinfunction "AGND_14") (pintype "unspecified"))
      (node (ref "U14") (pin "16") (pinfunction "AGND_16") (pintype "unspecified"))
      (node (ref "U14") (pin "19") (pinfunction "AGND_19") (pintype "unspecified"))
      (node (ref "U14") (pin "29") (pinfunction "GND_29") (pintype "unspecified"))
      (node (ref "U14") (pin "3") (pinfunction "AGND_3") (pintype "unspecified"))
      (node (ref "U14") (pin "48") (pinfunction "AGND_48") (pintype "unspecified"))
      (node (ref "U14") (pin "9") (pinfunction "AGND_9") (pintype "unspecified"))
      (node (ref "U15") (pin "1") (pinfunction "ADJ(GND)_1") (pintype "unspecified"))
      (node (ref "U16") (pin "2") (pinfunction "2_2") (pintype "unspecified"))
      (node (ref "U16") (pin "3") (pinfunction "3_3") (pintype "unspecified"))
      (node (ref "U16") (pin "6") (pinfunction "6_6") (pintype "unspecified"))
      (node (ref "U3") (pin "2") (pinfunction "2_2") (pintype "unspecified"))
    )
    (net (code "38") (name "Net-(J1-Pad9)") (class "Default")
      (node (ref "J1") (pin "9") (pinfunction "9_9") (pintype "unspecified"))
      (node (ref "R33") (pin "2") (pinfunction "2_2") (pintype "input"))
    )
    (net (code "39") (name "Net-(J1-Pad12)") (class "Default")
      (node (ref "J1") (pin "12") (pinfunction "12_12") (pintype "unspecified"))
      (node (ref "R34") (pin "2") (pinfunction "2_2") (pintype "input"))
    )
    (net (code "40") (name "Net-(LED1-K)") (class "Default")
      (node (ref "LED1") (pin "1") (pinfunction "K_1") (pintype "unspecified"))
      (node (ref "U3") (pin "1") (pinfunction "1_1") (pintype "unspecified"))
    )
    (net (code "41") (name "Net-(LED2-A)") (class "Default")
      (node (ref "LED2") (pin "2") (pinfunction "A_2") (pintype "unspecified"))
      (node (ref "U4") (pin "2") (pinfunction "2_2") (pintype "unspecified"))
    )
    (net (code "42") (name "Net-(LED3-A)") (class "Default")
      (node (ref "LED3") (pin "2") (pinfunction "A_2") (pintype "unspecified"))
      (node (ref "U5") (pin "2") (pinfunction "2_2") (pintype "unspecified"))
    )
    (net (code "43") (name "Net-(LED4-A)") (class "Default")
      (node (ref "LED4") (pin "2") (pinfunction "A_2") (pintype "unspecified"))
      (node (ref "U6") (pin "2") (pinfunction "2_2") (pintype "unspecified"))
    )
    (net (code "44") (name "Net-(LED5-A)") (class "Default")
      (node (ref "LED5") (pin "2") (pinfunction "A_2") (pintype "unspecified"))
      (node (ref "U7") (pin "2") (pinfunction "2_2") (pintype "unspecified"))
    )
    (net (code "45") (name "Net-(LED6-A)") (class "Default")
      (node (ref "LED6") (pin "2") (pinfunction "A_2") (pintype "unspecified"))
      (node (ref "U8") (pin "2") (pinfunction "2_2") (pintype "unspecified"))
    )
    (net (code "46") (name "Net-(LED7-A)") (class "Default")
      (node (ref "LED7") (pin "2") (pinfunction "A_2") (pintype "unspecified"))
      (node (ref "U9") (pin "2") (pinfunction "2_2") (pintype "unspecified"))
    )
    (net (code "47") (name "Net-(LED8-A)") (class "Default")
      (node (ref "LED8") (pin "2") (pinfunction "A_2") (pintype "unspecified"))
      (node (ref "U10") (pin "2") (pinfunction "2_2") (pintype "unspecified"))
    )
    (net (code "48") (name "Net-(LED9-A)") (class "Default")
      (node (ref "LED9") (pin "2") (pinfunction "A_2") (pintype "unspecified"))
      (node (ref "U11") (pin "2") (pinfunction "2_2") (pintype "unspecified"))
    )
    (net (code "49") (name "Net-(R17-Pad2)") (class "Default")
      (node (ref "R17") (pin "2") (pinfunction "2_2") (pintype "unspecified"))
      (node (ref "U14") (pin "23") (pinfunction "RSVD_23") (pintype "unspecified"))
    )
    (net (code "50") (name "Net-(R18-Pad1)") (class "Default")
      (node (ref "R18") (pin "1") (pinfunction "1_1") (pintype "unspecified"))
      (node (ref "U14") (pin "42") (pinfunction "RSVD_42") (pintype "unspecified"))
    )
    (net (code "51") (name "Net-(R19-Pad1)") (class "Default")
      (node (ref "R19") (pin "1") (pinfunction "1_1") (pintype "unspecified"))
      (node (ref "U14") (pin "41") (pinfunction "RSVD_41") (pintype "unspecified"))
    )
    (net (code "52") (name "Net-(R20-Pad1)") (class "Default")
      (node (ref "R20") (pin "1") (pinfunction "1_1") (pintype "unspecified"))
      (node (ref "U14") (pin "40") (pinfunction "RSVD_40") (pintype "unspecified"))
    )
    (net (code "53") (name "Net-(R21-Pad1)") (class "Default")
      (node (ref "R21") (pin "1") (pinfunction "1_1") (pintype "unspecified"))
      (node (ref "U14") (pin "39") (pinfunction "RSVD_39") (pintype "unspecified"))
    )
    (net (code "54") (name "Net-(R22-Pad1)") (class "Default")
      (node (ref "R22") (pin "1") (pinfunction "1_1") (pintype "unspecified"))
      (node (ref "U14") (pin "38") (pinfunction "RSVD_38") (pintype "unspecified"))
    )
    (net (code "55") (name "Net-(U1-EN)") (class "Default")
      (node (ref "C3") (pin "2") (pinfunction "2_2") (pintype "unspecified"))
      (node (ref "R5") (pin "1") (pinfunction "1_1") (pintype "unspecified"))
      (node (ref "U1") (pin "8") (pinfunction "EN_8") (pintype "unspecified"))
    )
    (net (code "56") (name "Net-(U14-1V2O)") (class "Default")
      (node (ref "C16") (pin "2") (pinfunction "2_2") (pintype "input"))
      (node (ref "U14") (pin "22") (pinfunction "1V2O_22") (pintype "unspecified"))
    )
    (net (code "57") (name "Net-(U14-EXRES1)") (class "Default")
      (node (ref "R16") (pin "2") (pinfunction "2_2") (pintype "input"))
      (node (ref "U14") (pin "10") (pinfunction "EXRES1_10") (pintype "unspecified"))
    )
    (net (code "58") (name "Net-(U14-TOCAP)") (class "Default")
      (node (ref "C14") (pin "2") (pinfunction "2_2") (pintype "input"))
      (node (ref "U14") (pin "20") (pinfunction "TOCAP_20") (pintype "unspecified"))
    )
    (net (code "59") (name "VCC3V3") (class "Default")
      (node (ref "C1") (pin "2") (pinfunction "2_2") (pintype "input"))
      (node (ref "C2") (pin "2") (pinfunction "2_2") (pintype "unspecified"))
      (node (ref "C20") (pin "2") (pinfunction "2_2") (pintype "unspecified"))
      (node (ref "C21") (pin "2") (pinfunction "2_2") (pintype "input"))
      (node (ref "C22") (pin "2") (pinfunction "2_2") (pintype "unspecified"))
      (node (ref "L2") (pin "1") (pinfunction "1_1") (pintype "unspecified"))
      (node (ref "R1") (pin "1") (pinfunction "1_1") (pintype "unspecified"))
      (node (ref "R23") (pin "2") (pinfunction "2_2") (pintype "unspecified"))
      (node (ref "R24") (pin "2") (pinfunction "2_2") (pintype "unspecified"))
      (node (ref "R25") (pin "2") (pinfunction "2_2") (pintype "unspecified"))
      (node (ref "R26") (pin "2") (pinfunction "2_2") (pintype "unspecified"))
      (node (ref "R27") (pin "2") (pinfunction "2_2") (pintype "unspecified"))
      (node (ref "R28") (pin "2") (pinfunction "2_2") (pintype "unspecified"))
      (node (ref "R33") (pin "1") (pinfunction "1_1") (pintype "input"))
      (node (ref "R34") (pin "1") (pinfunction "1_1") (pintype "input"))
      (node (ref "R5") (pin "2") (pinfunction "2_2") (pintype "unspecified"))
      (node (ref "U1") (pin "3") (pinfunction "3V3_3") (pintype "unspecified"))
      (node (ref "U10") (pin "1") (pinfunction "1_1") (pintype "unspecified"))
      (node (ref "U14") (pin "28") (pinfunction "VDD_28") (pintype "unspecified"))
      (node (ref "U15") (pin "2") (pinfunction "VOUT(TAB)_2") (pintype "unspecified"))
      (node (ref "U4") (pin "1") (pinfunction "1_1") (pintype "unspecified"))
      (node (ref "U5") (pin "1") (pinfunction "1_1") (pintype "unspecified"))
      (node (ref "U6") (pin "1") (pinfunction "1_1") (pintype "unspecified"))
      (node (ref "U7") (pin "1") (pinfunction "1_1") (pintype "unspecified"))
      (node (ref "U8") (pin "1") (pinfunction "1_1") (pintype "unspecified"))
      (node (ref "U9") (pin "1") (pinfunction "1_1") (pintype "unspecified"))
    )
    (net (code "60") (name "VCCA3V3") (class "Default")
      (node (ref "C13") (pin "2") (pinfunction "2_2") (pintype "unspecified"))
      (node (ref "C15") (pin "2") (pinfunction "2_2") (pintype "unspecified"))
      (node (ref "C23") (pin "1") (pinfunction "1_1") (pintype "unspecified"))
      (node (ref "L2") (pin "2") (pinfunction "2_2") (pintype "unspecified"))
      (node (ref "R35") (pin "1") (pinfunction "1_1") (pintype "input"))
      (node (ref "R36") (pin "1") (pinfunction "1_1") (pintype "input"))
      (node (ref "R37") (pin "1") (pinfunction "1_1") (pintype "input"))
      (node (ref "U14") (pin "11") (pinfunction "AVDD_11") (pintype "unspecified"))
      (node (ref "U14") (pin "15") (pinfunction "AVDD_15") (pintype "unspecified"))
      (node (ref "U14") (pin "17") (pinfunction "AVDD_17") (pintype "unspecified"))
      (node (ref "U14") (pin "21") (pinfunction "AVDD_21") (pintype "unspecified"))
      (node (ref "U14") (pin "4") (pinfunction "AVDD_4") (pintype "unspecified"))
      (node (ref "U14") (pin "8") (pinfunction "AVDD_8") (pintype "unspecified"))
    )
    (net (code "61") (name "unconnected-(J1-CHS_GND-Pad8)") (class "Default")
      (node (ref "J1") (pin "8") (pinfunction "CHS_GND_8") (pintype "unspecified+no_connect"))
    )
    (net (code "62") (name "unconnected-(J1-NC-Pad7)") (class "Default")
      (node (ref "J1") (pin "7") (pinfunction "NC_7") (pintype "unspecified+no_connect"))
    )
    (net (code "63") (name "unconnected-(U1-NC-Pad4)") (class "Default")
      (node (ref "U1") (pin "4") (pinfunction "NC_4") (pintype "unspecified+no_connect"))
    )
    (net (code "64") (name "unconnected-(U1-NC-Pad9)") (class "Default")
      (node (ref "U1") (pin "9") (pinfunction "NC_9") (pintype "unspecified+no_connect"))
    )
    (net (code "65") (name "unconnected-(U1-NC-Pad10)") (class "Default")
      (node (ref "U1") (pin "10") (pinfunction "NC_10") (pintype "unspecified+no_connect"))
    )
    (net (code "66") (name "unconnected-(U1-NC-Pad15)") (class "Default")
      (node (ref "U1") (pin "15") (pinfunction "NC_15") (pintype "unspecified+no_connect"))
    )
    (net (code "67") (name "unconnected-(U1-NC-Pad17)") (class "Default")
      (node (ref "U1") (pin "17") (pinfunction "NC_17") (pintype "unspecified+no_connect"))
    )
    (net (code "68") (name "unconnected-(U1-NC-Pad24)") (class "Default")
      (node (ref "U1") (pin "24") (pinfunction "NC_24") (pintype "unspecified+no_connect"))
    )
    (net (code "69") (name "unconnected-(U1-NC-Pad25)") (class "Default")
      (node (ref "U1") (pin "25") (pinfunction "NC_25") (pintype "unspecified+no_connect"))
    )
    (net (code "70") (name "unconnected-(U1-NC-Pad28)") (class "Default")
      (node (ref "U1") (pin "28") (pinfunction "NC_28") (pintype "unspecified+no_connect"))
    )
    (net (code "71") (name "unconnected-(U1-NC-Pad29)") (class "Default")
      (node (ref "U1") (pin "29") (pinfunction "NC_29") (pintype "unspecified+no_connect"))
    )
    (net (code "72") (name "unconnected-(U1-NC-Pad32)") (class "Default")
      (node (ref "U1") (pin "32") (pinfunction "NC_32") (pintype "unspecified+no_connect"))
    )
    (net (code "73") (name "unconnected-(U1-NC-Pad33)") (class "Default")
      (node (ref "U1") (pin "33") (pinfunction "NC_33") (pintype "unspecified+no_connect"))
    )
    (net (code "74") (name "unconnected-(U1-NC-Pad34)") (class "Default")
      (node (ref "U1") (pin "34") (pinfunction "NC_34") (pintype "unspecified+no_connect"))
    )
    (net (code "75") (name "unconnected-(U1-NC-Pad35)") (class "Default")
      (node (ref "U1") (pin "35") (pinfunction "NC_35") (pintype "unspecified+no_connect"))
    )
    (net (code "76") (name "unconnected-(U14-DNC-Pad7)") (class "Default")
      (node (ref "U14") (pin "7") (pinfunction "DNC_7") (pintype "unspecified+no_connect"))
    )
    (net (code "77") (name "unconnected-(U14-DUPLED-Pad26)") (class "Default")
      (node (ref "U14") (pin "26") (pinfunction "DUPLED_26") (pintype "unspecified+no_connect"))
    )
    (net (code "78") (name "unconnected-(U14-NC-Pad12)") (class "Default")
      (node (ref "U14") (pin "12") (pinfunction "NC_12") (pintype "unspecified+no_connect"))
    )
    (net (code "79") (name "unconnected-(U14-NC-Pad13)") (class "Default")
      (node (ref "U14") (pin "13") (pinfunction "NC_13") (pintype "unspecified+no_connect"))
    )
    (net (code "80") (name "unconnected-(U14-NC-Pad46)") (class "Default")
      (node (ref "U14") (pin "46") (pinfunction "NC_46") (pintype "unspecified+no_connect"))
    )
    (net (code "81") (name "unconnected-(U14-NC-Pad47)") (class "Default")
      (node (ref "U14") (pin "47") (pinfunction "NC_47") (pintype "unspecified+no_connect"))
    )
    (net (code "82") (name "unconnected-(U14-SPDLED-Pad24)") (class "Default")
      (node (ref "U14") (pin "24") (pinfunction "SPDLED_24") (pintype "unspecified+no_connect"))
    )
    (net (code "83") (name "unconnected-(U14-VBG-Pad18)") (class "Default")
      (node (ref "U14") (pin "18") (pinfunction "VBG_18") (pintype "unspecified+no_connect"))
    )
    (net (code "84") (name "unconnected-(U15-TAB-Pad4)") (class "Default")
      (node (ref "U15") (pin "4") (pinfunction "TAB_4") (pintype "unspecified+no_connect"))
    )
  )
)
